# Sheet1.net
KiCad netlist of a schematic drawn in Altium Designer
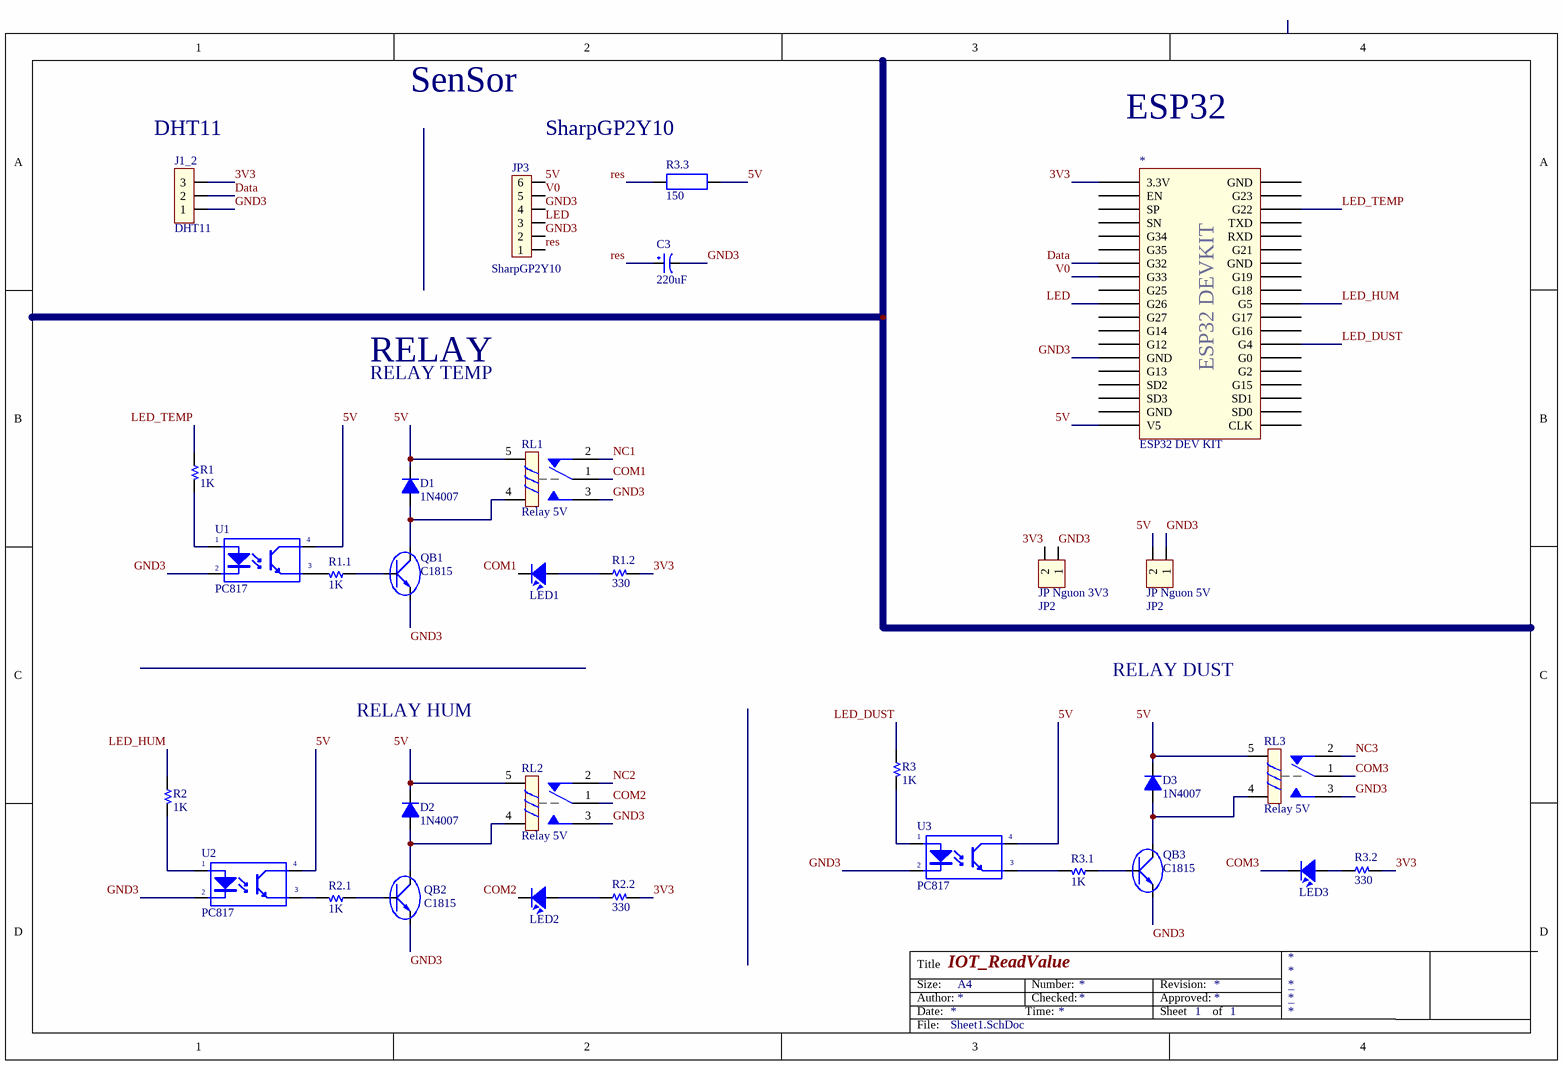
[diagram p0: Sheet1.SchDoc]

(export (version "E")
  (design (tool "Eeschema 10.0.6"))
  (components
    (comp (ref "*")
      (value "ESP32 DEV KIT")
      (footprint "ESP32 DEVKIT")
      (libsource (lib "Module") (part "ESP32 DEV KIT"))
    )
    (comp (ref "C3")
      (value "220uF")
      (footprint "CP1/2")
      (description "Cap P  0,1uF < 22uF , 16 - 50V")
      (libsource (lib "SCH_Lib_Devzone") (part "CP1"))
    )
    (comp (ref "D1")
      (value "1N4007")
      (footprint "D0.5A")
      (description "Diode 1A")
      (libsource (lib "SCH_Lib_Devzone") (part "D1A"))
    )
    (comp (ref "D2")
      (value "1N4007")
      (footprint "D0.5A")
      (description "Diode 1A")
      (libsource (lib "SCH_Lib_Devzone") (part "D1A"))
    )
    (comp (ref "D3")
      (value "1N4007")
      (footprint "D0.5A")
      (description "Diode 1A")
      (libsource (lib "SCH_Lib_Devzone") (part "D1A"))
    )
    (comp (ref "J1_2")
      (value "DHT11")
      (footprint "JP3H")
      (description "Jumper 3")
      (libsource (lib "SCH_Lib_Devzone") (part "JP3"))
    )
    (comp (ref "JP Nguon 3V3")
      (value "JP2")
      (footprint "CON2")
      (description "Connector 2")
      (libsource (lib "SCH_Lib_Devzone") (part "Con2"))
    )
    (comp (ref "JP Nguon 5V")
      (value "JP2")
      (footprint "CON2")
      (description "Connector 2")
      (libsource (lib "SCH_Lib_Devzone") (part "Con2"))
    )
    (comp (ref "JP3")
      (value "SharpGP2Y10")
      (footprint "JP6")
      (description "JP6 PIN")
      (libsource (lib "SCH_Lib_Devzone") (part "JP6"))
    )
    (comp (ref "LED1")
      (value "LED")
      (footprint "LED-5TRED")
      (description "LED Single colour Green and Red")
      (libsource (lib "SCH_Lib_Devzone") (part "LED"))
    )
    (comp (ref "LED2")
      (value "LED")
      (footprint "LED-5TRED")
      (description "LED Single colour Green and Red")
      (libsource (lib "SCH_Lib_Devzone") (part "LED"))
    )
    (comp (ref "LED3")
      (value "LED")
      (footprint "LED-5TRED")
      (description "LED Single colour Green and Red")
      (libsource (lib "SCH_Lib_Devzone") (part "LED"))
    )
    (comp (ref "QB1")
      (value "C1815")
      (footprint "QTO-247")
      (description "Transistor Power Supply")
      (libsource (lib "SCH_Lib_Devzone") (part "D718"))
    )
    (comp (ref "QB2")
      (value "C1815")
      (footprint "QTO-247")
      (description "Transistor Power Supply")
      (libsource (lib "SCH_Lib_Devzone") (part "D718"))
    )
    (comp (ref "QB3")
      (value "C1815")
      (footprint "QTO-247")
      (description "Transistor Power Supply")
      (libsource (lib "SCH_Lib_Devzone") (part "D718"))
    )
    (comp (ref "R1")
      (value "1K")
      (footprint "R 1/4W/300")
      (description "Resistor")
      (libsource (lib "chipfc_libs") (part "Resistor"))
    )
    (comp (ref "R1.1")
      (value "1K")
      (footprint "R 1/4W/300")
      (description "Resistor")
      (libsource (lib "chipfc_libs") (part "Resistor"))
    )
    (comp (ref "R1.2")
      (value "330")
      (footprint "R 1/4W/300")
      (description "Resistor")
      (libsource (lib "chipfc_libs") (part "Resistor"))
    )
    (comp (ref "R2")
      (value "1K")
      (footprint "R 1/4W/300")
      (description "Resistor")
      (libsource (lib "chipfc_libs") (part "Resistor"))
    )
    (comp (ref "R2.1")
      (value "1K")
      (footprint "R 1/4W/300")
      (description "Resistor")
      (libsource (lib "chipfc_libs") (part "Resistor"))
    )
    (comp (ref "R2.2")
      (value "330")
      (footprint "R 1/4W/300")
      (description "Resistor")
      (libsource (lib "chipfc_libs") (part "Resistor"))
    )
    (comp (ref "R3")
      (value "1K")
      (footprint "R 1/4W/300")
      (description "Resistor")
      (libsource (lib "chipfc_libs") (part "Resistor"))
    )
    (comp (ref "R3.1")
      (value "1K")
      (footprint "R 1/4W/300")
      (description "Resistor")
      (libsource (lib "chipfc_libs") (part "Resistor"))
    )
    (comp (ref "R3.2")
      (value "330")
      (footprint "R 1/4W/300")
      (description "Resistor")
      (libsource (lib "chipfc_libs") (part "Resistor"))
    )
    (comp (ref "R3.3")
      (value "150")
      (footprint "Res_15mm")
      (description "Resistor 1W")
      (libsource (lib "SCH_Lib_Devzone") (part "R1W"))
    )
    (comp (ref "RL1")
      (value "Relay 5V")
      (footprint "RL_SPDT_10A")
      (description "Relay SPDT,10A - 12VDC 5 Pin")
      (libsource (lib "SCH_Lib_Devzone") (part "Relay 1"))
    )
    (comp (ref "RL2")
      (value "Relay 5V")
      (footprint "RL_SPDT_10A")
      (description "Relay SPDT,10A - 12VDC 5 Pin")
      (libsource (lib "SCH_Lib_Devzone") (part "Relay 1"))
    )
    (comp (ref "RL3")
      (value "Relay 5V")
      (footprint "RL_SPDT_10A")
      (description "Relay SPDT,10A - 12VDC 5 Pin")
      (libsource (lib "SCH_Lib_Devzone") (part "Relay 1"))
    )
    (comp (ref "U1")
      (value "PC817")
      (footprint "DIP4/W0.3")
      (description "Single Opto")
      (libsource (lib "SCH_Lib_Devzone") (part "PC817"))
    )
    (comp (ref "U2")
      (value "PC817")
      (footprint "DIP4/W0.3")
      (description "Single Opto")
      (libsource (lib "SCH_Lib_Devzone") (part "PC817"))
    )
    (comp (ref "U3")
      (value "PC817")
      (footprint "DIP4/W0.3")
      (description "Single Opto")
      (libsource (lib "SCH_Lib_Devzone") (part "PC817"))
    )
  )
  (nets
    (net (code "1") (name "/3V3") (class "Default")
      (node (ref "*") (pin "1") (pinfunction "3.3V_1") (pintype "passive"))
      (node (ref "J1_2") (pin "3") (pinfunction "3_3") (pintype "passive"))
      (node (ref "JP Nguon 3V3") (pin "2") (pinfunction "2_2") (pintype "passive"))
      (node (ref "R1.2") (pin "2") (pinfunction "2_2") (pintype "passive"))
      (node (ref "R2.2") (pin "2") (pinfunction "2_2") (pintype "passive"))
      (node (ref "R3.2") (pin "2") (pinfunction "2_2") (pintype "passive"))
    )
    (net (code "2") (name "/5V") (class "Default")
      (node (ref "*") (pin "19") (pinfunction "V5_19") (pintype "passive"))
      (node (ref "D1") (pin "2") (pinfunction "K_2") (pintype "passive"))
      (node (ref "D2") (pin "2") (pinfunction "K_2") (pintype "passive"))
      (node (ref "D3") (pin "2") (pinfunction "K_2") (pintype "passive"))
      (node (ref "JP Nguon 5V") (pin "2") (pinfunction "2_2") (pintype "passive"))
      (node (ref "JP3") (pin "6") (pinfunction "6_6") (pintype "passive"))
      (node (ref "R3.3") (pin "2") (pinfunction "2_2") (pintype "passive"))
      (node (ref "RL1") (pin "5") (pinfunction "5_5") (pintype "passive"))
      (node (ref "RL2") (pin "5") (pinfunction "5_5") (pintype "passive"))
      (node (ref "RL3") (pin "5") (pinfunction "5_5") (pintype "passive"))
      (node (ref "U1") (pin "4") (pinfunction "C_4") (pintype "passive"))
      (node (ref "U2") (pin "4") (pinfunction "C_4") (pintype "passive"))
      (node (ref "U3") (pin "4") (pinfunction "C_4") (pintype "passive"))
    )
    (net (code "3") (name "/COM1") (class "Default")
      (node (ref "LED1") (pin "2") (pinfunction "2_2") (pintype "passive"))
      (node (ref "RL1") (pin "1") (pinfunction "1_1") (pintype "passive"))
    )
    (net (code "4") (name "/COM2") (class "Default")
      (node (ref "LED2") (pin "2") (pinfunction "2_2") (pintype "passive"))
      (node (ref "RL2") (pin "1") (pinfunction "1_1") (pintype "passive"))
    )
    (net (code "5") (name "/COM3") (class "Default")
      (node (ref "LED3") (pin "2") (pinfunction "2_2") (pintype "passive"))
      (node (ref "RL3") (pin "1") (pinfunction "1_1") (pintype "passive"))
    )
    (net (code "6") (name "/Data") (class "Default")
      (node (ref "*") (pin "7") (pinfunction "G32_7") (pintype "passive"))
      (node (ref "J1_2") (pin "2") (pinfunction "2_2") (pintype "passive"))
    )
    (net (code "7") (name "/GND3") (class "Default")
      (node (ref "*") (pin "14") (pinfunction "GND_14") (pintype "passive"))
      (node (ref "C3") (pin "2") (pinfunction "2_2") (pintype "passive"))
      (node (ref "J1_2") (pin "1") (pinfunction "1_1") (pintype "passive"))
      (node (ref "JP Nguon 3V3") (pin "1") (pinfunction "1_1") (pintype "passive"))
      (node (ref "JP Nguon 5V") (pin "1") (pinfunction "1_1") (pintype "passive"))
      (node (ref "JP3") (pin "2") (pinfunction "2_2") (pintype "passive"))
      (node (ref "JP3") (pin "4") (pinfunction "4_4") (pintype "passive"))
      (node (ref "QB1") (pin "3") (pinfunction "E_3") (pintype "passive"))
      (node (ref "QB2") (pin "3") (pinfunction "E_3") (pintype "passive"))
      (node (ref "QB3") (pin "3") (pinfunction "E_3") (pintype "passive"))
      (node (ref "RL1") (pin "3") (pinfunction "3_3") (pintype "passive"))
      (node (ref "RL2") (pin "3") (pinfunction "3_3") (pintype "passive"))
      (node (ref "RL3") (pin "3") (pinfunction "3_3") (pintype "passive"))
      (node (ref "U1") (pin "2") (pinfunction "K_2") (pintype "passive"))
      (node (ref "U2") (pin "2") (pinfunction "K_2") (pintype "passive"))
      (node (ref "U3") (pin "2") (pinfunction "K_2") (pintype "passive"))
    )
    (net (code "8") (name "/LED") (class "Default")
      (node (ref "*") (pin "10") (pinfunction "G26_10") (pintype "passive"))
      (node (ref "JP3") (pin "3") (pinfunction "3_3") (pintype "passive"))
    )
    (net (code "9") (name "/LED_DUST") (class "Default")
      (node (ref "*") (pin "26") (pinfunction "G4_26") (pintype "passive"))
      (node (ref "R3") (pin "1") (pinfunction "1_1") (pintype "passive"))
    )
    (net (code "10") (name "/LED_HUM") (class "Default")
      (node (ref "*") (pin "29") (pinfunction "G5_29") (pintype "passive"))
      (node (ref "R2") (pin "1") (pinfunction "1_1") (pintype "passive"))
    )
    (net (code "11") (name "/LED_TEMP") (class "Default")
      (node (ref "*") (pin "36") (pinfunction "G22_36") (pintype "passive"))
      (node (ref "R1") (pin "1") (pinfunction "1_1") (pintype "passive"))
    )
    (net (code "12") (name "/NC1") (class "Default")
      (node (ref "RL1") (pin "2") (pinfunction "2_2") (pintype "passive"))
    )
    (net (code "13") (name "/NC2") (class "Default")
      (node (ref "RL2") (pin "2") (pinfunction "2_2") (pintype "passive"))
    )
    (net (code "14") (name "/NC3") (class "Default")
      (node (ref "RL3") (pin "2") (pinfunction "2_2") (pintype "passive"))
    )
    (net (code "15") (name "/V0") (class "Default")
      (node (ref "*") (pin "8") (pinfunction "G33_8") (pintype "passive"))
      (node (ref "JP3") (pin "5") (pinfunction "5_5") (pintype "passive"))
    )
    (net (code "16") (name "/res") (class "Default")
      (node (ref "C3") (pin "1") (pinfunction "1_1") (pintype "passive"))
      (node (ref "JP3") (pin "1") (pinfunction "1_1") (pintype "passive"))
      (node (ref "R3.3") (pin "1") (pinfunction "1_1") (pintype "passive"))
    )
    (net (code "17") (name "Net-(D1-A)") (class "Default")
      (node (ref "D1") (pin "1") (pinfunction "A_1") (pintype "passive"))
      (node (ref "QB1") (pin "2") (pinfunction "C_2") (pintype "passive"))
      (node (ref "RL1") (pin "4") (pinfunction "4_4") (pintype "passive"))
    )
    (net (code "18") (name "Net-(D2-A)") (class "Default")
      (node (ref "D2") (pin "1") (pinfunction "A_1") (pintype "passive"))
      (node (ref "QB2") (pin "2") (pinfunction "C_2") (pintype "passive"))
      (node (ref "RL2") (pin "4") (pinfunction "4_4") (pintype "passive"))
    )
    (net (code "19") (name "Net-(D3-A)") (class "Default")
      (node (ref "D3") (pin "1") (pinfunction "A_1") (pintype "passive"))
      (node (ref "QB3") (pin "2") (pinfunction "C_2") (pintype "passive"))
      (node (ref "RL3") (pin "4") (pinfunction "4_4") (pintype "passive"))
    )
    (net (code "20") (name "Net-(LED1-Pad1)") (class "Default")
      (node (ref "LED1") (pin "1") (pinfunction "1_1") (pintype "passive"))
      (node (ref "R1.2") (pin "1") (pinfunction "1_1") (pintype "passive"))
    )
    (net (code "21") (name "Net-(LED2-Pad1)") (class "Default")
      (node (ref "LED2") (pin "1") (pinfunction "1_1") (pintype "passive"))
      (node (ref "R2.2") (pin "1") (pinfunction "1_1") (pintype "passive"))
    )
    (net (code "22") (name "Net-(LED3-Pad1)") (class "Default")
      (node (ref "LED3") (pin "1") (pinfunction "1_1") (pintype "passive"))
      (node (ref "R3.2") (pin "1") (pinfunction "1_1") (pintype "passive"))
    )
    (net (code "23") (name "Net-(QB1-B)") (class "Default")
      (node (ref "QB1") (pin "1") (pinfunction "B_1") (pintype "passive"))
      (node (ref "R1.1") (pin "1") (pinfunction "1_1") (pintype "passive"))
    )
    (net (code "24") (name "Net-(QB2-B)") (class "Default")
      (node (ref "QB2") (pin "1") (pinfunction "B_1") (pintype "passive"))
      (node (ref "R2.1") (pin "1") (pinfunction "1_1") (pintype "passive"))
    )
    (net (code "25") (name "Net-(QB3-B)") (class "Default")
      (node (ref "QB3") (pin "1") (pinfunction "B_1") (pintype "passive"))
      (node (ref "R3.1") (pin "1") (pinfunction "1_1") (pintype "passive"))
    )
    (net (code "26") (name "Net-(U1-A)") (class "Default")
      (node (ref "R1") (pin "2") (pinfunction "2_2") (pintype "passive"))
      (node (ref "U1") (pin "1") (pinfunction "A_1") (pintype "passive"))
    )
    (net (code "27") (name "Net-(U1-E)") (class "Default")
      (node (ref "R1.1") (pin "2") (pinfunction "2_2") (pintype "passive"))
      (node (ref "U1") (pin "3") (pinfunction "E_3") (pintype "passive"))
    )
    (net (code "28") (name "Net-(U2-A)") (class "Default")
      (node (ref "R2") (pin "2") (pinfunction "2_2") (pintype "passive"))
      (node (ref "U2") (pin "1") (pinfunction "A_1") (pintype "passive"))
    )
    (net (code "29") (name "Net-(U2-E)") (class "Default")
      (node (ref "R2.1") (pin "2") (pinfunction "2_2") (pintype "passive"))
      (node (ref "U2") (pin "3") (pinfunction "E_3") (pintype "passive"))
    )
    (net (code "30") (name "Net-(U3-A)") (class "Default")
      (node (ref "R3") (pin "2") (pinfunction "2_2") (pintype "passive"))
      (node (ref "U3") (pin "1") (pinfunction "A_1") (pintype "passive"))
    )
    (net (code "31") (name "Net-(U3-E)") (class "Default")
      (node (ref "R3.1") (pin "2") (pinfunction "2_2") (pintype "passive"))
      (node (ref "U3") (pin "3") (pinfunction "E_3") (pintype "passive"))
    )
    (net (code "32") (name "unconnected-(*-CLK-Pad20)") (class "Default")
      (node (ref "*") (pin "20") (pinfunction "CLK_20") (pintype "passive"))
    )
    (net (code "33") (name "unconnected-(*-EN-Pad2)") (class "Default")
      (node (ref "*") (pin "2") (pinfunction "EN_2") (pintype "passive"))
    )
    (net (code "34") (name "unconnected-(*-G0-Pad25)") (class "Default")
      (node (ref "*") (pin "25") (pinfunction "G0_25") (pintype "passive"))
    )
    (net (code "35") (name "unconnected-(*-G2-Pad24)") (class "Default")
      (node (ref "*") (pin "24") (pinfunction "G2_24") (pintype "passive"))
    )
    (net (code "36") (name "unconnected-(*-G12-Pad13)") (class "Default")
      (node (ref "*") (pin "13") (pinfunction "G12_13") (pintype "passive"))
    )
    (net (code "37") (name "unconnected-(*-G13-Pad15)") (class "Default")
      (node (ref "*") (pin "15") (pinfunction "G13_15") (pintype "passive"))
    )
    (net (code "38") (name "unconnected-(*-G14-Pad12)") (class "Default")
      (node (ref "*") (pin "12") (pinfunction "G14_12") (pintype "passive"))
    )
    (net (code "39") (name "unconnected-(*-G15-Pad23)") (class "Default")
      (node (ref "*") (pin "23") (pinfunction "G15_23") (pintype "passive"))
    )
    (net (code "40") (name "unconnected-(*-G16-Pad27)") (class "Default")
      (node (ref "*") (pin "27") (pinfunction "G16_27") (pintype "passive"))
    )
    (net (code "41") (name "unconnected-(*-G17-Pad28)") (class "Default")
      (node (ref "*") (pin "28") (pinfunction "G17_28") (pintype "passive"))
    )
    (net (code "42") (name "unconnected-(*-G18-Pad30)") (class "Default")
      (node (ref "*") (pin "30") (pinfunction "G18_30") (pintype "passive"))
    )
    (net (code "43") (name "unconnected-(*-G19-Pad31)") (class "Default")
      (node (ref "*") (pin "31") (pinfunction "G19_31") (pintype "passive"))
    )
    (net (code "44") (name "unconnected-(*-G21-Pad33)") (class "Default")
      (node (ref "*") (pin "33") (pinfunction "G21_33") (pintype "passive"))
    )
    (net (code "45") (name "unconnected-(*-G23-Pad37)") (class "Default")
      (node (ref "*") (pin "37") (pinfunction "G23_37") (pintype "passive"))
    )
    (net (code "46") (name "unconnected-(*-G25-Pad9)") (class "Default")
      (node (ref "*") (pin "9") (pinfunction "G25_9") (pintype "passive"))
    )
    (net (code "47") (name "unconnected-(*-G27-Pad11)") (class "Default")
      (node (ref "*") (pin "11") (pinfunction "G27_11") (pintype "passive"))
    )
    (net (code "48") (name "unconnected-(*-G34-Pad5)") (class "Default")
      (node (ref "*") (pin "5") (pinfunction "G34_5") (pintype "passive"))
    )
    (net (code "49") (name "unconnected-(*-G35-Pad6)") (class "Default")
      (node (ref "*") (pin "6") (pinfunction "G35_6") (pintype "passive"))
    )
    (net (code "50") (name "unconnected-(*-GND-Pad18)") (class "Default")
      (node (ref "*") (pin "18") (pinfunction "GND_18") (pintype "passive"))
    )
    (net (code "51") (name "unconnected-(*-GND-Pad32)") (class "Default")
      (node (ref "*") (pin "32") (pinfunction "GND_32") (pintype "passive"))
    )
    (net (code "52") (name "unconnected-(*-GND-Pad38)") (class "Default")
      (node (ref "*") (pin "38") (pinfunction "GND_38") (pintype "passive"))
    )
    (net (code "53") (name "unconnected-(*-RXD-Pad34)") (class "Default")
      (node (ref "*") (pin "34") (pinfunction "RXD_34") (pintype "passive"))
    )
    (net (code "54") (name "unconnected-(*-SD0-Pad21)") (class "Default")
      (node (ref "*") (pin "21") (pinfunction "SD0_21") (pintype "passive"))
    )
    (net (code "55") (name "unconnected-(*-SD1-Pad22)") (class "Default")
      (node (ref "*") (pin "22") (pinfunction "SD1_22") (pintype "passive"))
    )
    (net (code "56") (name "unconnected-(*-SD2-Pad16)") (class "Default")
      (node (ref "*") (pin "16") (pinfunction "SD2_16") (pintype "passive"))
    )
    (net (code "57") (name "unconnected-(*-SD3-Pad17)") (class "Default")
      (node (ref "*") (pin "17") (pinfunction "SD3_17") (pintype "passive"))
    )
    (net (code "58") (name "unconnected-(*-SN-Pad4)") (class "Default")
      (node (ref "*") (pin "4") (pinfunction "SN_4") (pintype "passive"))
    )
    (net (code "59") (name "unconnected-(*-SP-Pad3)") (class "Default")
      (node (ref "*") (pin "3") (pinfunction "SP_3") (pintype "passive"))
    )
    (net (code "60") (name "unconnected-(*-TXD-Pad35)") (class "Default")
      (node (ref "*") (pin "35") (pinfunction "TXD_35") (pintype "passive"))
    )
  )
)
